# XiaomiWeatherStation.net
KiCad netlist of a schematic drawn in EAGLE
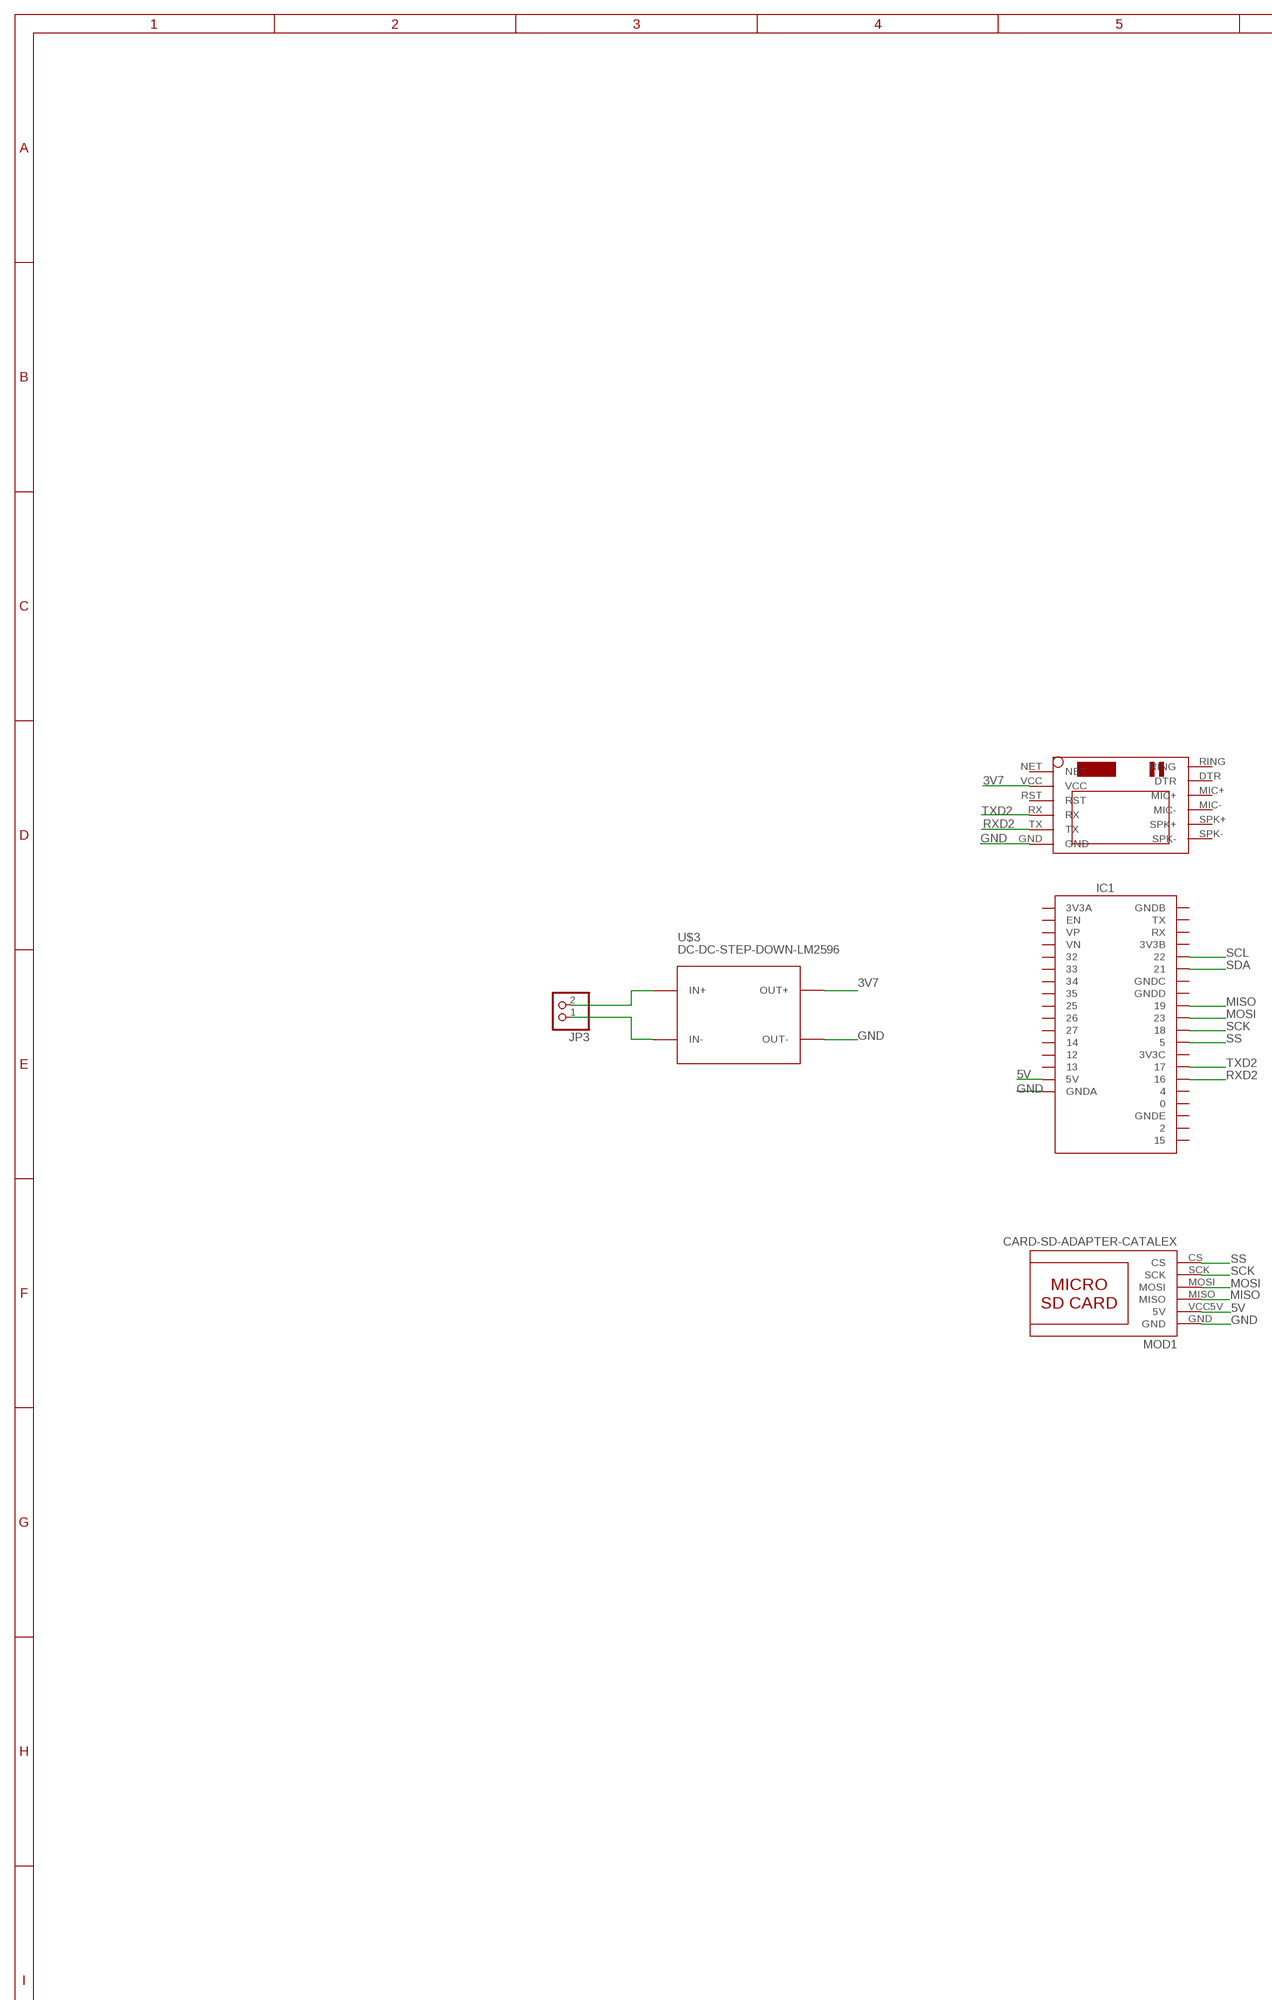
[diagram p0: schematic, sheet 1, part 1 of 2]
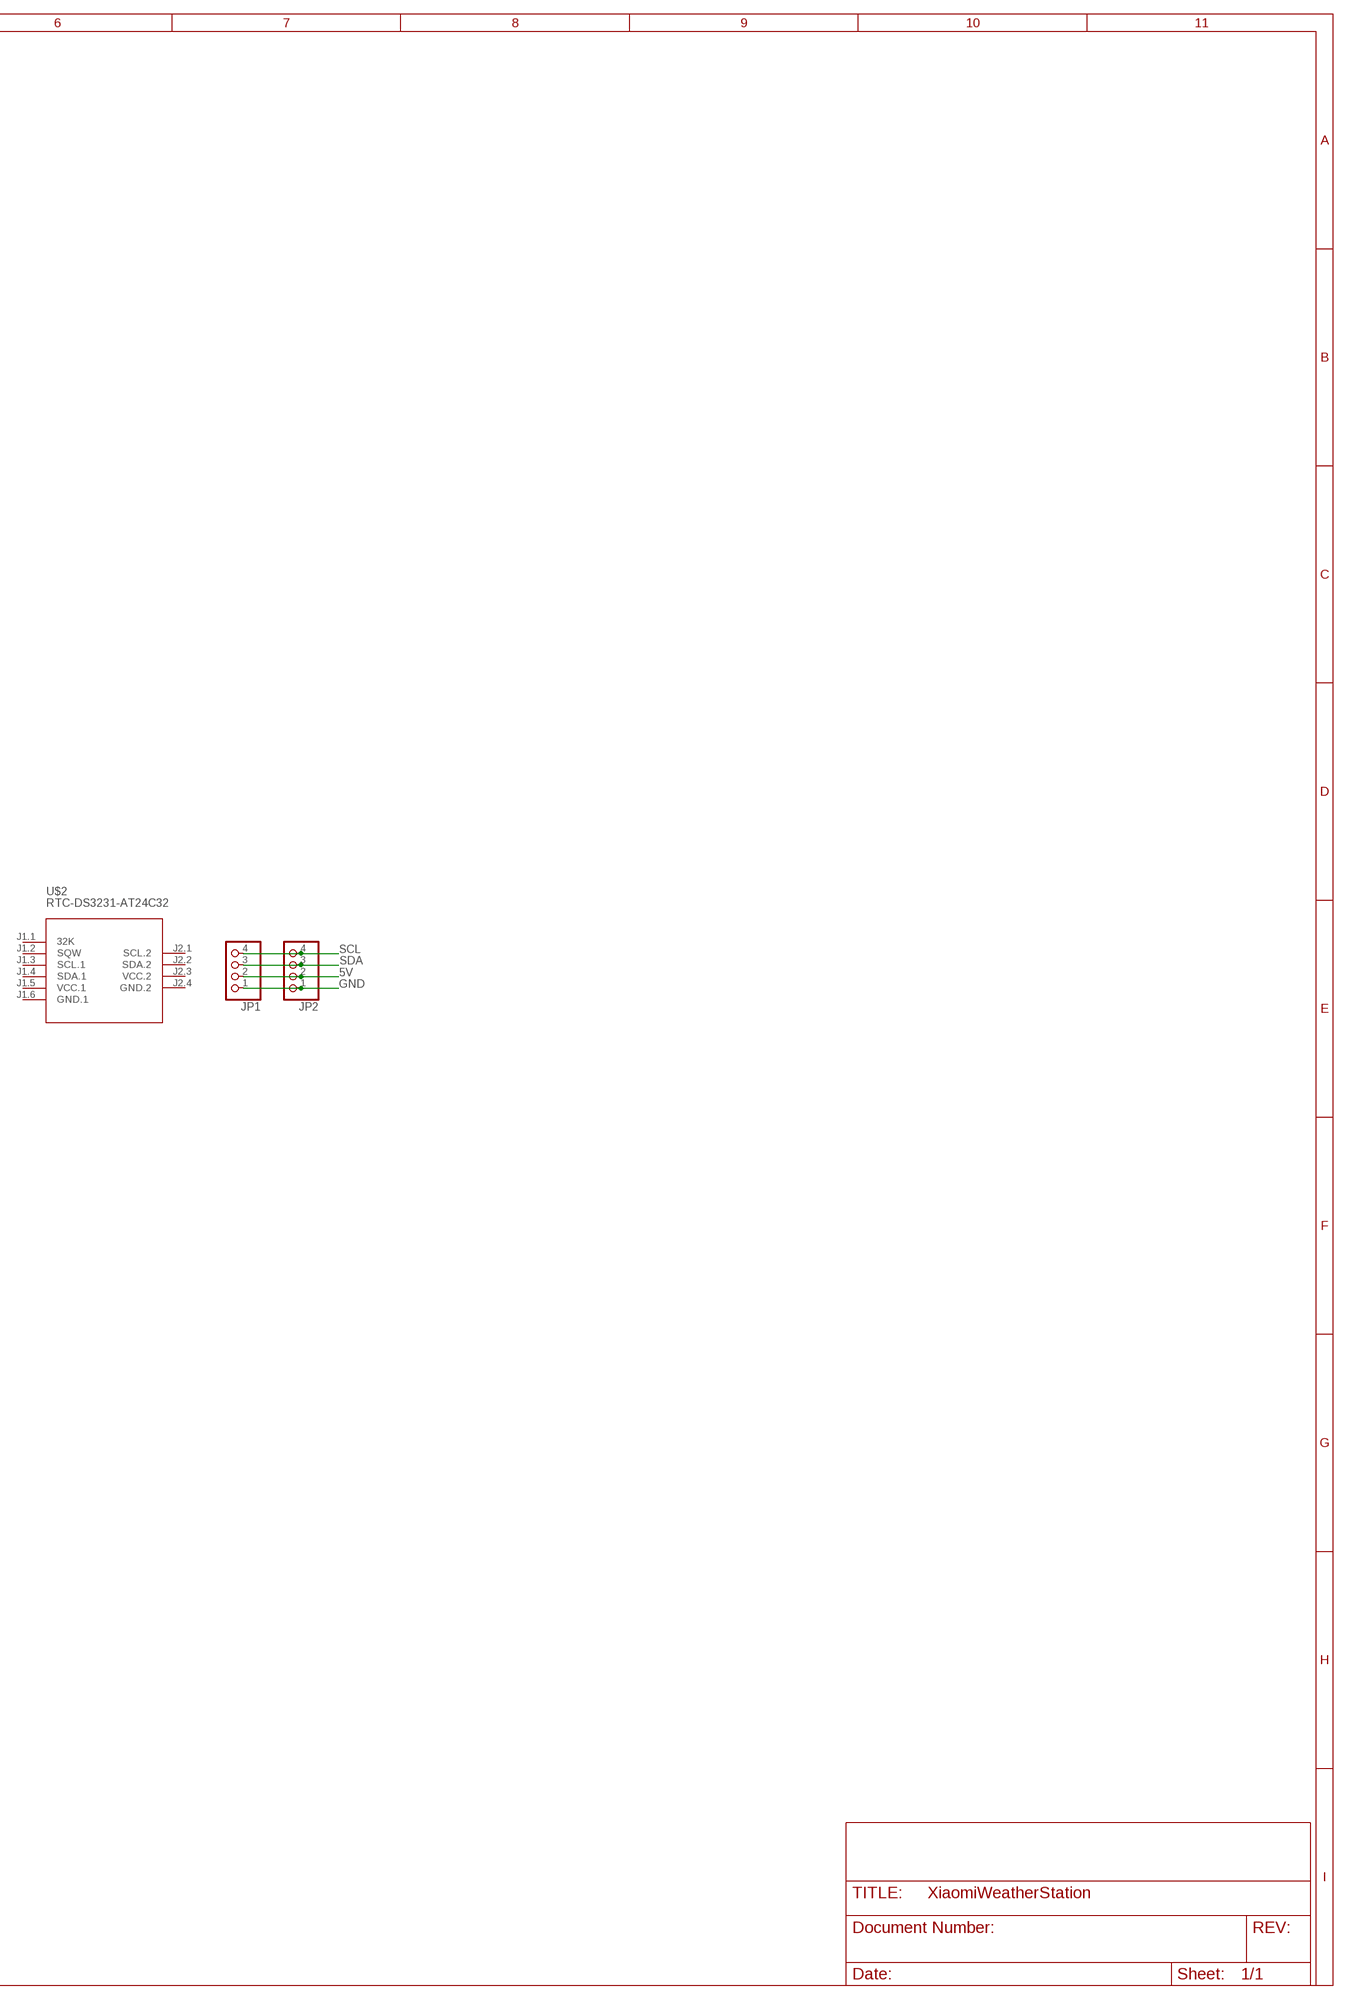
[diagram p1: schematic, sheet 1, part 2 of 2]

(export (version "E")
  (design (tool "Eeschema 10.0.6"))
  (components
    (comp (ref "IC1")
      (value "SSFD_LOLIN32_WEMOS_CHINA_W_BATT")
      (footprint "eagle-import:SSFD_LOLIN32_WEMOS_CHINA_W_BATT")
      (libsource (lib "eagle-import") (part "SSFD_LOLIN32_WEMOS_CHINA_W_BATT"))
    )
    (comp (ref "JP1")
      (value "PINHD-1X4")
      (footprint "eagle-import:1X04")
      (libsource (lib "eagle-import") (part "PINHD-1X4"))
    )
    (comp (ref "JP2")
      (value "PINHD-1X4")
      (footprint "eagle-import:1X04")
      (libsource (lib "eagle-import") (part "PINHD-1X4"))
    )
    (comp (ref "JP3")
      (value "PINHD-1X2")
      (footprint "eagle-import:1X02")
      (libsource (lib "eagle-import") (part "PINHD-1X2"))
    )
    (comp (ref "MOD1")
      (value "CARD-SD-ADAPTER-CATALEX")
      (footprint "eagle-import:CARD-SD-ADAPTER-CATALEX")
      (libsource (lib "eagle-import") (part "CARD-SD-ADAPTER-CATALEX"))
    )
    (comp (ref "U$1")
      (value "SIM800LMODULE")
      (footprint "eagle-import:SIM800LMODULE")
      (libsource (lib "eagle-import") (part "SIM800LMODULE"))
    )
    (comp (ref "U$2")
      (value "RTC-DS3231-AT24C32")
      (footprint "eagle-import:RTC-DS3231-AT24C32")
      (libsource (lib "eagle-import") (part "RTC-DS3231-AT24C32"))
    )
    (comp (ref "U$3")
      (value "DC-DC-STEP-DOWN-LM2596")
      (footprint "eagle-import:DC-DC-STEP-DOWN-LM2596")
      (libsource (lib "eagle-import") (part "DC-DC-STEP-DOWN-LM2596"))
    )
  )
  (nets
    (net (code "1") (name "/3V7") (class "Default")
      (node (ref "U$1") (pin "VCC") (pinfunction "VCC_VCC") (pintype "bidirectional"))
      (node (ref "U$3") (pin "OUT+") (pinfunction "OUT+_OUT+") (pintype "bidirectional"))
    )
    (net (code "2") (name "/5V") (class "Default")
      (node (ref "IC1") (pin "5V") (pinfunction "5V_5V") (pintype "bidirectional"))
      (node (ref "JP1") (pin "2") (pinfunction "2_2") (pintype "passive"))
      (node (ref "JP2") (pin "2") (pinfunction "2_2") (pintype "passive"))
      (node (ref "MOD1") (pin "VCC5V") (pinfunction "5V_VCC5V") (pintype "power_in"))
    )
    (net (code "3") (name "/GND") (class "Default")
      (node (ref "IC1") (pin "GNDA") (pinfunction "GNDA_GNDA") (pintype "bidirectional"))
      (node (ref "JP1") (pin "1") (pinfunction "1_1") (pintype "passive"))
      (node (ref "JP2") (pin "1") (pinfunction "1_1") (pintype "passive"))
      (node (ref "MOD1") (pin "GND") (pinfunction "GND_GND") (pintype "power_in"))
      (node (ref "U$1") (pin "GND") (pinfunction "GND_GND") (pintype "bidirectional"))
      (node (ref "U$3") (pin "OUT-") (pinfunction "OUT-_OUT-") (pintype "bidirectional"))
    )
    (net (code "4") (name "/GND.1") (class "Default")
      (node (ref "U$2") (pin "J1.6") (pinfunction "GND.1_J1.6") (pintype "power_in"))
    )
    (net (code "5") (name "/GND.2") (class "Default")
      (node (ref "U$2") (pin "J2.4") (pinfunction "GND.2_J2.4") (pintype "power_in"))
    )
    (net (code "6") (name "/MISO") (class "Default")
      (node (ref "IC1") (pin "19") (pinfunction "19_19") (pintype "bidirectional"))
      (node (ref "MOD1") (pin "MISO") (pinfunction "MISO_MISO") (pintype "bidirectional"))
    )
    (net (code "7") (name "/MOSI") (class "Default")
      (node (ref "IC1") (pin "23") (pinfunction "23_23") (pintype "bidirectional"))
      (node (ref "MOD1") (pin "MOSI") (pinfunction "MOSI_MOSI") (pintype "bidirectional"))
    )
    (net (code "8") (name "/RXD2") (class "Default")
      (node (ref "IC1") (pin "16") (pinfunction "16_16") (pintype "bidirectional"))
      (node (ref "U$1") (pin "TX") (pinfunction "TX_TX") (pintype "bidirectional"))
    )
    (net (code "9") (name "/SCK") (class "Default")
      (node (ref "IC1") (pin "18") (pinfunction "18_18") (pintype "bidirectional"))
      (node (ref "MOD1") (pin "SCK") (pinfunction "SCK_SCK") (pintype "bidirectional"))
    )
    (net (code "10") (name "/SCL") (class "Default")
      (node (ref "IC1") (pin "22") (pinfunction "22_22") (pintype "bidirectional"))
      (node (ref "JP1") (pin "4") (pinfunction "4_4") (pintype "passive"))
      (node (ref "JP2") (pin "4") (pinfunction "4_4") (pintype "passive"))
    )
    (net (code "11") (name "/SDA") (class "Default")
      (node (ref "IC1") (pin "21") (pinfunction "21_21") (pintype "bidirectional"))
      (node (ref "JP1") (pin "3") (pinfunction "3_3") (pintype "passive"))
      (node (ref "JP2") (pin "3") (pinfunction "3_3") (pintype "passive"))
    )
    (net (code "12") (name "/SS") (class "Default")
      (node (ref "IC1") (pin "5") (pinfunction "5_5") (pintype "bidirectional"))
      (node (ref "MOD1") (pin "CS") (pinfunction "CS_CS") (pintype "bidirectional"))
    )
    (net (code "13") (name "/TXD2") (class "Default")
      (node (ref "IC1") (pin "17") (pinfunction "17_17") (pintype "bidirectional"))
      (node (ref "U$1") (pin "RX") (pinfunction "RX_RX") (pintype "bidirectional"))
    )
    (net (code "14") (name "/VCC.1") (class "Default")
      (node (ref "U$2") (pin "J1.5") (pinfunction "VCC.1_J1.5") (pintype "power_in"))
    )
    (net (code "15") (name "/VCC.2") (class "Default")
      (node (ref "U$2") (pin "J2.3") (pinfunction "VCC.2_J2.3") (pintype "power_in"))
    )
    (net (code "16") (name "Net-(JP3-Pad1)") (class "Default")
      (node (ref "JP3") (pin "1") (pinfunction "1_1") (pintype "passive"))
      (node (ref "U$3") (pin "IN-") (pinfunction "IN-_IN-") (pintype "bidirectional"))
    )
    (net (code "17") (name "Net-(JP3-Pad2)") (class "Default")
      (node (ref "JP3") (pin "2") (pinfunction "2_2") (pintype "passive"))
      (node (ref "U$3") (pin "IN+") (pinfunction "IN+_IN+") (pintype "bidirectional"))
    )
    (net (code "18") (name "unconnected-(IC1-Pad0)") (class "Default")
      (node (ref "IC1") (pin "0") (pinfunction "0_0") (pintype "bidirectional"))
    )
    (net (code "19") (name "unconnected-(IC1-Pad2)") (class "Default")
      (node (ref "IC1") (pin "2") (pinfunction "2_2") (pintype "bidirectional"))
    )
    (net (code "20") (name "unconnected-(IC1-Pad3V3A)") (class "Default")
      (node (ref "IC1") (pin "3V3A") (pinfunction "3V3A_3V3A") (pintype "bidirectional"))
    )
    (net (code "21") (name "unconnected-(IC1-Pad3V3B)") (class "Default")
      (node (ref "IC1") (pin "3V3B") (pinfunction "3V3B_3V3B") (pintype "bidirectional"))
    )
    (net (code "22") (name "unconnected-(IC1-Pad3V3C)") (class "Default")
      (node (ref "IC1") (pin "3V3C") (pinfunction "3V3C_3V3C") (pintype "bidirectional"))
    )
    (net (code "23") (name "unconnected-(IC1-Pad4)") (class "Default")
      (node (ref "IC1") (pin "4") (pinfunction "4_4") (pintype "bidirectional"))
    )
    (net (code "24") (name "unconnected-(IC1-Pad12)") (class "Default")
      (node (ref "IC1") (pin "12") (pinfunction "12_12") (pintype "bidirectional"))
    )
    (net (code "25") (name "unconnected-(IC1-Pad13)") (class "Default")
      (node (ref "IC1") (pin "13") (pinfunction "13_13") (pintype "bidirectional"))
    )
    (net (code "26") (name "unconnected-(IC1-Pad14)") (class "Default")
      (node (ref "IC1") (pin "14") (pinfunction "14_14") (pintype "bidirectional"))
    )
    (net (code "27") (name "unconnected-(IC1-Pad15)") (class "Default")
      (node (ref "IC1") (pin "15") (pinfunction "15_15") (pintype "bidirectional"))
    )
    (net (code "28") (name "unconnected-(IC1-Pad25)") (class "Default")
      (node (ref "IC1") (pin "25") (pinfunction "25_25") (pintype "bidirectional"))
    )
    (net (code "29") (name "unconnected-(IC1-Pad26)") (class "Default")
      (node (ref "IC1") (pin "26") (pinfunction "26_26") (pintype "bidirectional"))
    )
    (net (code "30") (name "unconnected-(IC1-Pad27)") (class "Default")
      (node (ref "IC1") (pin "27") (pinfunction "27_27") (pintype "bidirectional"))
    )
    (net (code "31") (name "unconnected-(IC1-Pad32)") (class "Default")
      (node (ref "IC1") (pin "32") (pinfunction "32_32") (pintype "bidirectional"))
    )
    (net (code "32") (name "unconnected-(IC1-Pad33)") (class "Default")
      (node (ref "IC1") (pin "33") (pinfunction "33_33") (pintype "bidirectional"))
    )
    (net (code "33") (name "unconnected-(IC1-Pad34)") (class "Default")
      (node (ref "IC1") (pin "34") (pinfunction "34_34") (pintype "bidirectional"))
    )
    (net (code "34") (name "unconnected-(IC1-Pad35)") (class "Default")
      (node (ref "IC1") (pin "35") (pinfunction "35_35") (pintype "bidirectional"))
    )
    (net (code "35") (name "unconnected-(IC1-PadEN)") (class "Default")
      (node (ref "IC1") (pin "EN") (pinfunction "EN_EN") (pintype "bidirectional"))
    )
    (net (code "36") (name "unconnected-(IC1-PadGNDB)") (class "Default")
      (node (ref "IC1") (pin "GNDB") (pinfunction "GNDB_GNDB") (pintype "bidirectional"))
    )
    (net (code "37") (name "unconnected-(IC1-PadGNDC)") (class "Default")
      (node (ref "IC1") (pin "GNDC") (pinfunction "GNDC_GNDC") (pintype "bidirectional"))
    )
    (net (code "38") (name "unconnected-(IC1-PadGNDD)") (class "Default")
      (node (ref "IC1") (pin "GNDD") (pinfunction "GNDD_GNDD") (pintype "bidirectional"))
    )
    (net (code "39") (name "unconnected-(IC1-PadGNDE)") (class "Default")
      (node (ref "IC1") (pin "GNDE") (pinfunction "GNDE_GNDE") (pintype "bidirectional"))
    )
    (net (code "40") (name "unconnected-(IC1-PadRX)") (class "Default")
      (node (ref "IC1") (pin "RX") (pinfunction "RX_RX") (pintype "bidirectional"))
    )
    (net (code "41") (name "unconnected-(IC1-PadTX)") (class "Default")
      (node (ref "IC1") (pin "TX") (pinfunction "TX_TX") (pintype "bidirectional"))
    )
    (net (code "42") (name "unconnected-(IC1-PadVN)") (class "Default")
      (node (ref "IC1") (pin "VN") (pinfunction "VN_VN") (pintype "bidirectional"))
    )
    (net (code "43") (name "unconnected-(IC1-PadVP)") (class "Default")
      (node (ref "IC1") (pin "VP") (pinfunction "VP_VP") (pintype "bidirectional"))
    )
    (net (code "44") (name "unconnected-(U$1-PadDTR)") (class "Default")
      (node (ref "U$1") (pin "DTR") (pinfunction "DTR_DTR") (pintype "bidirectional"))
    )
    (net (code "45") (name "unconnected-(U$1-PadMIC+)") (class "Default")
      (node (ref "U$1") (pin "MIC+") (pinfunction "MIC+_MIC+") (pintype "bidirectional"))
    )
    (net (code "46") (name "unconnected-(U$1-PadMIC-)") (class "Default")
      (node (ref "U$1") (pin "MIC-") (pinfunction "MIC-_MIC-") (pintype "bidirectional"))
    )
    (net (code "47") (name "unconnected-(U$1-PadNET)") (class "Default")
      (node (ref "U$1") (pin "NET") (pinfunction "NET_NET") (pintype "bidirectional"))
    )
    (net (code "48") (name "unconnected-(U$1-PadRING)") (class "Default")
      (node (ref "U$1") (pin "RING") (pinfunction "RING_RING") (pintype "bidirectional"))
    )
    (net (code "49") (name "unconnected-(U$1-PadRST)") (class "Default")
      (node (ref "U$1") (pin "RST") (pinfunction "RST_RST") (pintype "bidirectional"))
    )
    (net (code "50") (name "unconnected-(U$1-PadSPK+)") (class "Default")
      (node (ref "U$1") (pin "SPK+") (pinfunction "SPK+_SPK+") (pintype "bidirectional"))
    )
    (net (code "51") (name "unconnected-(U$1-PadSPK-)") (class "Default")
      (node (ref "U$1") (pin "SPK-") (pinfunction "SPK-_SPK-") (pintype "bidirectional"))
    )
    (net (code "52") (name "unconnected-(U$2-32K-PadJ1.1)") (class "Default")
      (node (ref "U$2") (pin "J1.1") (pinfunction "32K_J1.1") (pintype "bidirectional"))
    )
    (net (code "53") (name "unconnected-(U$2-SCL.1-PadJ1.3)") (class "Default")
      (node (ref "U$2") (pin "J1.3") (pinfunction "SCL.1_J1.3") (pintype "bidirectional"))
    )
    (net (code "54") (name "unconnected-(U$2-SCL.2-PadJ2.1)") (class "Default")
      (node (ref "U$2") (pin "J2.1") (pinfunction "SCL.2_J2.1") (pintype "bidirectional"))
    )
    (net (code "55") (name "unconnected-(U$2-SDA.1-PadJ1.4)") (class "Default")
      (node (ref "U$2") (pin "J1.4") (pinfunction "SDA.1_J1.4") (pintype "bidirectional"))
    )
    (net (code "56") (name "unconnected-(U$2-SDA.2-PadJ2.2)") (class "Default")
      (node (ref "U$2") (pin "J2.2") (pinfunction "SDA.2_J2.2") (pintype "bidirectional"))
    )
    (net (code "57") (name "unconnected-(U$2-SQW-PadJ1.2)") (class "Default")
      (node (ref "U$2") (pin "J1.2") (pinfunction "SQW_J1.2") (pintype "bidirectional"))
    )
  )
)
